# H2E_Port.net
KiCad netlist of a schematic drawn in Altium Designer
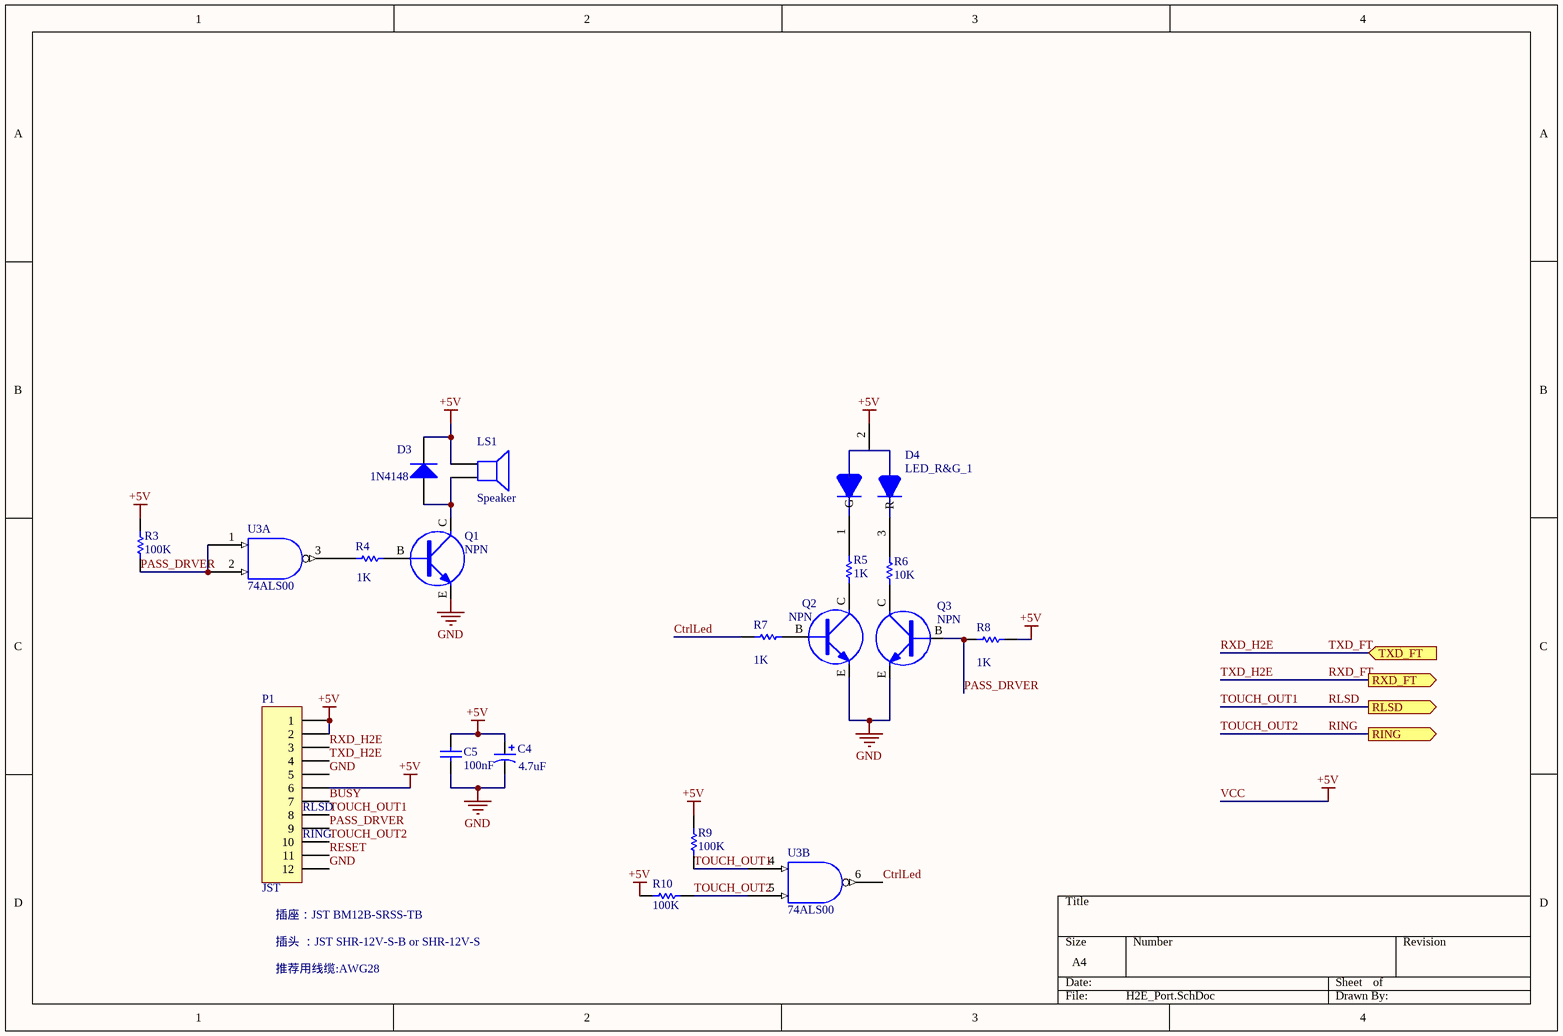
[diagram p0: H2E_Port.SchDoc]

(export (version "E")
  (design (tool "Eeschema 10.0.6"))
  (components
    (comp (ref "C4")
      (value "4.7uF")
      (footprint "T3528")
      (fields (field (name "Comment") "CAP+"))
      (libsource (lib "PV") (part "CAP+"))
    )
    (comp (ref "C5")
      (value "100nF")
      (footprint "C0603")
      (description "Capacitor")
      (fields (field (name "Comment") "CAP"))
      (libsource (lib "PV") (part "CAP"))
    )
    (comp (ref "D3")
      (value "1N4148")
      (footprint "D1206")
      (description "High Conductance Fast Diode")
      (libsource (lib "Miscellaneous Devices") (part "Diode 1N4148"))
    )
    (comp (ref "D4") (value "LED_R&G_1") (footprint "LED_R&G") (libsource (lib "PV") (part "LED_R&G_1")))
    (comp (ref "LS1")
      (value "Speaker")
      (footprint "BUZZER")
      (description "Loudspeaker")
      (fields (field (name "PUBLISHER") "Altium Limited"))
      (libsource (lib "Miscellaneous Devices") (part "Speaker"))
    )
    (comp (ref "P1")
      (value "JST")
      (footprint "JST BM12B-SRSS-TB")
      (description "Header, 12-Pin")
      (fields (field (name "PUBLISHER") "Altium Limited"))
      (libsource (lib "Miscellaneous Connectors") (part "Header 12"))
    )
    (comp (ref "Q1")
      (value "NPN")
      (footprint "SOT23/BEC")
      (description "NPN Transistor")
      (libsource (lib "PV") (part "NPN"))
    )
    (comp (ref "Q2")
      (value "NPN")
      (footprint "SOT23/BEC")
      (description "NPN Transistor")
      (libsource (lib "PV") (part "NPN"))
    )
    (comp (ref "Q3")
      (value "NPN")
      (footprint "SOT23/BEC")
      (description "NPN Transistor")
      (libsource (lib "PV") (part "NPN"))
    )
    (comp (ref "R3")
      (value "100K")
      (footprint "R0603")
      (description "Resistor")
      (fields (field (name "Comment") "Res1") (field (name "PUBLISHER") "Altium Limited"))
      (libsource (lib "Miscellaneous Devices") (part "Res1"))
    )
    (comp (ref "R4")
      (value "1K")
      (footprint "R0603")
      (description "Resistor")
      (fields (field (name "Comment") "Res1") (field (name "PUBLISHER") "Altium Limited"))
      (libsource (lib "Miscellaneous Devices") (part "Res1"))
    )
    (comp (ref "R5")
      (value "1K")
      (footprint "R0603")
      (description "Resistor")
      (fields (field (name "Comment") "Res1") (field (name "PUBLISHER") "Altium Limited"))
      (libsource (lib "Miscellaneous Devices") (part "Res1"))
    )
    (comp (ref "R6")
      (value "10K")
      (footprint "R0603")
      (description "Resistor")
      (fields (field (name "Comment") "Res1") (field (name "PUBLISHER") "Altium Limited"))
      (libsource (lib "Miscellaneous Devices") (part "Res1"))
    )
    (comp (ref "R7")
      (value "1K")
      (footprint "R0603")
      (description "Resistor")
      (fields (field (name "Comment") "Res1") (field (name "PUBLISHER") "Altium Limited"))
      (libsource (lib "Miscellaneous Devices") (part "Res1"))
    )
    (comp (ref "R8")
      (value "1K")
      (footprint "R0603")
      (description "Resistor")
      (fields (field (name "Comment") "Res1") (field (name "PUBLISHER") "Altium Limited"))
      (libsource (lib "Miscellaneous Devices") (part "Res1"))
    )
    (comp (ref "R9")
      (value "100K")
      (footprint "R0603")
      (description "Resistor")
      (fields (field (name "Comment") "Res1") (field (name "PUBLISHER") "Altium Limited"))
      (libsource (lib "Miscellaneous Devices") (part "Res1"))
    )
    (comp (ref "R10")
      (value "100K")
      (footprint "R0603")
      (description "Resistor")
      (fields (field (name "Comment") "Res1") (field (name "PUBLISHER") "Altium Limited"))
      (libsource (lib "Miscellaneous Devices") (part "Res1"))
    )
    (comp (ref "U3") (value "74ALS00") (footprint "SOIC-14") (libsource (lib "shuai74 TTL") (part "74ALS00")))
  )
  (nets
    (net (code "1") (name "+5V") (class "Default")
      (node (ref "C4") (pin "1") (pinfunction "1_1") (pintype "passive"))
      (node (ref "C5") (pin "2") (pinfunction "2_2") (pintype "passive"))
      (node (ref "D3") (pin "2") (pinfunction "K_2") (pintype "passive"))
      (node (ref "D4") (pin "2") (pinfunction "P_2") (pintype "passive"))
      (node (ref "LS1") (pin "1") (pinfunction "1_1") (pintype "passive"))
      (node (ref "P1") (pin "1") (pinfunction "1_1") (pintype "passive"))
      (node (ref "P1") (pin "2") (pinfunction "2_2") (pintype "passive"))
      (node (ref "P1") (pin "6") (pinfunction "6_6") (pintype "passive"))
      (node (ref "R10") (pin "2") (pinfunction "2_2") (pintype "passive"))
      (node (ref "R3") (pin "2") (pinfunction "2_2") (pintype "passive"))
      (node (ref "R8") (pin "2") (pinfunction "2_2") (pintype "passive"))
      (node (ref "R9") (pin "2") (pinfunction "2_2") (pintype "passive"))
      (node (ref "U3") (pin "14") (pinfunction "VCC_14") (pintype "power_in"))
    )
    (net (code "2") (name "/BUSY") (class "Default")
      (node (ref "P1") (pin "7") (pinfunction "7_7") (pintype "passive"))
    )
    (net (code "3") (name "/CtrlLed") (class "Default")
      (node (ref "R7") (pin "1") (pinfunction "1_1") (pintype "passive"))
      (node (ref "U3") (pin "6") (pintype "output"))
    )
    (net (code "4") (name "/PASS_DRVER") (class "Default")
      (node (ref "P1") (pin "9") (pinfunction "9_9") (pintype "passive"))
      (node (ref "Q3") (pin "B") (pinfunction "B_B") (pintype "passive"))
      (node (ref "R3") (pin "1") (pinfunction "1_1") (pintype "passive"))
      (node (ref "R8") (pin "1") (pinfunction "1_1") (pintype "passive"))
      (node (ref "U3") (pin "1") (pintype "input"))
      (node (ref "U3") (pin "2") (pintype "input"))
    )
    (net (code "5") (name "/RESET") (class "Default")
      (node (ref "P1") (pin "11") (pinfunction "11_11") (pintype "passive"))
    )
    (net (code "6") (name "/RING") (class "Default")
      (node (ref "P1") (pin "10") (pinfunction "10_10") (pintype "passive"))
      (node (ref "R10") (pin "1") (pinfunction "1_1") (pintype "passive"))
      (node (ref "U3") (pin "5") (pintype "input"))
    )
    (net (code "7") (name "/RLSD") (class "Default")
      (node (ref "P1") (pin "8") (pinfunction "8_8") (pintype "passive"))
      (node (ref "R9") (pin "1") (pinfunction "1_1") (pintype "passive"))
      (node (ref "U3") (pin "4") (pintype "input"))
    )
    (net (code "8") (name "/RXD_FT") (class "Default")
      (node (ref "P1") (pin "4") (pinfunction "4_4") (pintype "passive"))
    )
    (net (code "9") (name "/RXD_H2E") (class "Default")
      (node (ref "P1") (pin "3") (pinfunction "3_3") (pintype "passive"))
    )
    (net (code "10") (name "GND") (class "Default")
      (node (ref "C4") (pin "2") (pinfunction "2_2") (pintype "passive"))
      (node (ref "C5") (pin "1") (pinfunction "1_1") (pintype "passive"))
      (node (ref "P1") (pin "12") (pinfunction "12_12") (pintype "passive"))
      (node (ref "P1") (pin "5") (pinfunction "5_5") (pintype "passive"))
      (node (ref "Q1") (pin "E") (pinfunction "E_E") (pintype "passive"))
      (node (ref "Q2") (pin "E") (pinfunction "E_E") (pintype "passive"))
      (node (ref "Q3") (pin "E") (pinfunction "E_E") (pintype "passive"))
      (node (ref "U3") (pin "7") (pinfunction "GND_7") (pintype "power_in"))
    )
    (net (code "11") (name "Net-(D3-A)") (class "Default")
      (node (ref "D3") (pin "1") (pinfunction "A_1") (pintype "passive"))
      (node (ref "LS1") (pin "2") (pinfunction "2_2") (pintype "passive"))
      (node (ref "Q1") (pin "C") (pinfunction "C_C") (pintype "passive"))
    )
    (net (code "12") (name "Net-(D4-G)") (class "Default")
      (node (ref "D4") (pin "1") (pinfunction "G_1") (pintype "passive"))
      (node (ref "R5") (pin "2") (pinfunction "2_2") (pintype "passive"))
    )
    (net (code "13") (name "Net-(D4-R)") (class "Default")
      (node (ref "D4") (pin "3") (pinfunction "R_3") (pintype "passive"))
      (node (ref "R6") (pin "2") (pinfunction "2_2") (pintype "passive"))
    )
    (net (code "14") (name "Net-(Q1-PadB)") (class "Default")
      (node (ref "Q1") (pin "B") (pinfunction "B_B") (pintype "passive"))
      (node (ref "R4") (pin "2") (pinfunction "2_2") (pintype "passive"))
    )
    (net (code "15") (name "Net-(Q2-PadB)") (class "Default")
      (node (ref "Q2") (pin "B") (pinfunction "B_B") (pintype "passive"))
      (node (ref "R7") (pin "2") (pinfunction "2_2") (pintype "passive"))
    )
    (net (code "16") (name "Net-(Q2-PadC)") (class "Default")
      (node (ref "Q2") (pin "C") (pinfunction "C_C") (pintype "passive"))
      (node (ref "R5") (pin "1") (pinfunction "1_1") (pintype "passive"))
    )
    (net (code "17") (name "Net-(Q3-PadC)") (class "Default")
      (node (ref "Q3") (pin "C") (pinfunction "C_C") (pintype "passive"))
      (node (ref "R6") (pin "1") (pinfunction "1_1") (pintype "passive"))
    )
    (net (code "18") (name "Net-(R4-Pad1)") (class "Default")
      (node (ref "R4") (pin "1") (pinfunction "1_1") (pintype "passive"))
      (node (ref "U3") (pin "3") (pintype "output"))
    )
  )
)
